# GTL3_Inverter.net
KiCad netlist of a schematic drawn in Altium Designer
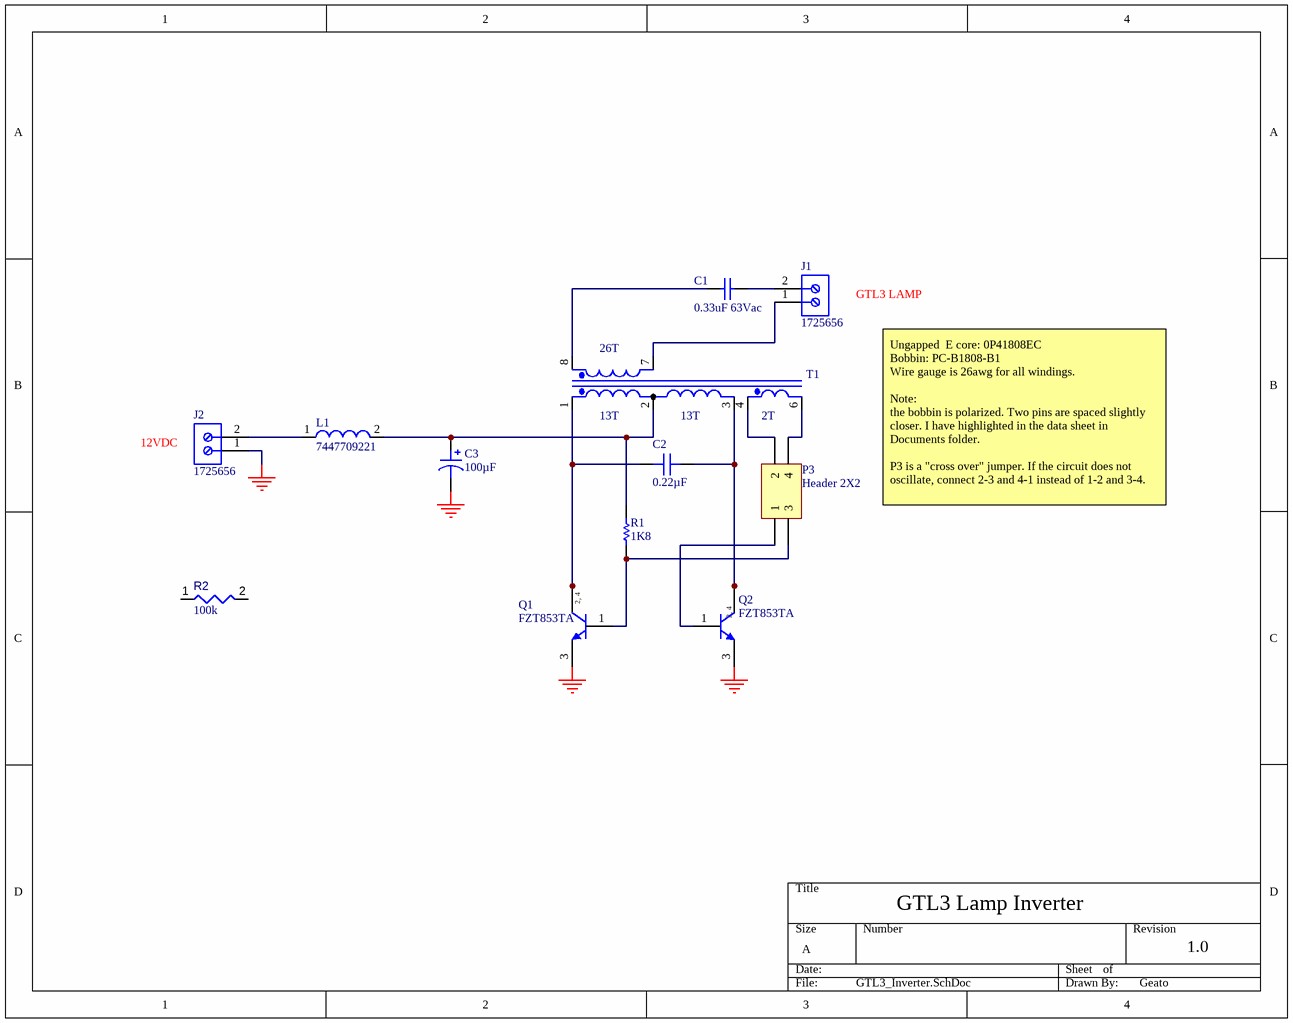
[diagram p0: GTL3_Inverter.SchDoc]

(export (version "E")
  (design (tool "Eeschema 10.0.6"))
  (components
    (comp (ref "C1")
      (value "0.33uF 63Vac")
      (footprint "CAPC6050X33M")
      (description "Film Capacitors 100Vdc 0.33uF 10% AEC-Q200")
      (fields (field (name "TOLERANCE") "10%"))
      (libsource (lib "Greg Eaton") (part "CAP-NP-2"))
    )
    (comp (ref "C2")
      (value "0.22µF")
      (footprint "CAP FILM 2416")
      (description "CAP FILM 0.22UF 2% 50VDC 2416")
      (fields
        (field (name "PART NUMBER") "ECH-U1H224GX9")
        (field (name "MANUFACTURER") "Panasonic Electronic Components")
      )
      (libsource (lib "Celestial Altium Library - altium_library") (part "Capacitor"))
    )
    (comp (ref "C3")
      (value "100µF")
      (footprint "CAP ALSMD 8.3MM H10.5MM")
      (description "CAP ALUM SMD 105C 100UF 50VDC")
      (fields (field (name "PART NUMBER") "EDH107M050A9MAA") (field (name "MANUFACTURER") "KEMET"))
      (libsource (lib "Celestial Altium Library - altium_library") (part "Polarised Capacitor"))
    )
    (comp (ref "J1")
      (value "1725656")
      (footprint "PHOE-1725656-2")
      (description "Male Header, Pitch 2.54 mm, 1 x 2 Position, Height 9 mm, Tail Length 3.5 mm")
      (fields (field (name "MANUFACTURER") "Phoenix Contact"))
      (libsource (lib "Altium Content Vault") (part "CN-1P-F-TB2"))
    )
    (comp (ref "J2")
      (value "1725656")
      (footprint "PHOE-1725656-2")
      (description "Male Header, Pitch 2.54 mm, 1 x 2 Position, Height 9 mm, Tail Length 3.5 mm")
      (fields (field (name "MANUFACTURER") "Phoenix Contact"))
      (libsource (lib "Altium Content Vault") (part "CN-1P-F-TB2"))
    )
    (comp (ref "L1")
      (value "7447709221")
      (footprint "WE-PD-XXL")
      (description "SMD-Shielded Power Inductor WE-PD, L = 220 µH")
      (fields (field (name "AML PART NUMBER") "IND-S0011"))
      (libsource (lib "Altium Content Vault") (part "CMP-0227-00173-1"))
    )
    (comp (ref "P3")
      (value "Header 2X2")
      (footprint "HDR2X2")
      (description "Header, 2-Pin, Dual row")
      (fields (field (name "PUBLISHER") "Altium Limited"))
      (libsource (lib "Miscellaneous Connectors") (part "Header 2X2"))
    )
    (comp (ref "Q1")
      (value "FZT853TA")
      (footprint "DIOD-SOT223-4_V")
      (description "NPN Medium Power Transistor, 100 V, 6 A, -55 to 150 degC, 4-Pin SOT223, RoHS, Tape and Reel")
      (fields (field (name "MANUFACTURER") "DiodesIncorporated"))
      (libsource (lib "Altium Content Vault") (part "BJT-NPN-BCEC-4"))
    )
    (comp (ref "Q2")
      (value "FZT853TA")
      (footprint "DIOD-SOT223-4_V")
      (description "NPN Medium Power Transistor, 100 V, 6 A, -55 to 150 degC, 4-Pin SOT223, RoHS, Tape and Reel")
      (fields (field (name "MANUFACTURER") "DiodesIncorporated"))
      (libsource (lib "Altium Content Vault") (part "BJT-NPN-BCEC-4"))
    )
    (comp (ref "R1")
      (value "1K8")
      (footprint "RESC0805(2012)_L")
      (description "1K8 0.125W 1% 0805 (2012 Metric)  SMD")
      (fields (field (name "POWER") "0.125 W") (field (name "TOLERANCE") "1 %"))
      (libsource (lib "Altium Content Vault") (part "CMP-1013-00537-1"))
    )
    (comp (ref "R2")
      (value "100k")
      (footprint "RESC1608X55X25ML10T15")
      (description "Chip Resistor, 100 KOhm, +/- 1%, 0.1 W, -55 to 155 degC, 0603 (1608 Metric)")
      (fields (field (name "POWER") "100mW") (field (name "TOLERANCE") "1%"))
      (libsource (lib "Greg Eaton") (part "RES-2"))
    )
    (comp (ref "T1")
      (value "Trans5_Royer")
      (footprint "PCB1808B1")
      (description "Four-winding Transformer (Non-Ideal)")
      (fields (field (name "PUBLISHER") "Altium Limited"))
      (libsource (lib "Miscellaneous Devices") (part "Trans5_Royer"))
    )
  )
  (nets
    (net (code "1") (name "GND") (class "Default")
      (node (ref "C3") (pin "2") (pinfunction "2_2") (pintype "passive"))
      (node (ref "J2") (pin "1") (pinfunction "1_1") (pintype "passive"))
      (node (ref "Q1") (pin "3") (pinfunction "E_3") (pintype "passive"))
      (node (ref "Q2") (pin "3") (pinfunction "E_3") (pintype "passive"))
    )
    (net (code "2") (name "Net-(C1-Pad2)") (class "Default")
      (node (ref "C1") (pin "2") (pinfunction "2_2") (pintype "passive"))
      (node (ref "J1") (pin "2") (pinfunction "2_2") (pintype "passive"))
    )
    (net (code "3") (name "Net-(J2-Pad2)") (class "Default")
      (node (ref "J2") (pin "2") (pinfunction "2_2") (pintype "passive"))
      (node (ref "L1") (pin "1") (pinfunction "1_1") (pintype "passive"))
    )
    (net (code "4") (name "Net-(Q1-B)") (class "Default")
      (node (ref "P3") (pin "3") (pinfunction "3_3") (pintype "passive"))
      (node (ref "Q1") (pin "1") (pinfunction "B_1") (pintype "passive"))
      (node (ref "R1") (pin "1") (pinfunction "1_1") (pintype "passive"))
    )
    (net (code "5") (name "Net-(Q2-B)") (class "Default")
      (node (ref "P3") (pin "1") (pinfunction "1_1") (pintype "passive"))
      (node (ref "Q2") (pin "1") (pinfunction "B_1") (pintype "passive"))
    )
    (net (code "6") (name "Net-(T1-Pri+)") (class "Default")
      (node (ref "C1") (pin "1") (pinfunction "1_1") (pintype "passive"))
      (node (ref "T1") (pin "8") (pinfunction "Pri+_8") (pintype "passive"))
    )
    (net (code "7") (name "Net-(T1-Pri-)") (class "Default")
      (node (ref "J1") (pin "1") (pinfunction "1_1") (pintype "passive"))
      (node (ref "T1") (pin "7") (pinfunction "Pri-_7") (pintype "passive"))
    )
    (net (code "8") (name "Net-(T1-Sec1+)") (class "Default")
      (node (ref "C2") (pin "2") (pinfunction "2_2") (pintype "passive"))
      (node (ref "Q1") (pin "2") (pinfunction "C_2") (pintype "passive"))
      (node (ref "Q1") (pin "4") (pinfunction "C_4") (pintype "passive"))
      (node (ref "T1") (pin "1") (pinfunction "Sec1+_1") (pintype "passive"))
    )
    (net (code "9") (name "Net-(T1-Sec1-)") (class "Default")
      (node (ref "C3") (pin "1") (pinfunction "1_1") (pintype "passive"))
      (node (ref "L1") (pin "2") (pinfunction "2_2") (pintype "passive"))
      (node (ref "R1") (pin "2") (pinfunction "2_2") (pintype "passive"))
      (node (ref "T1") (pin "2") (pinfunction "Sec1-_2") (pintype "passive"))
    )
    (net (code "10") (name "Net-(T1-Sec2-)") (class "Default")
      (node (ref "C2") (pin "1") (pinfunction "1_1") (pintype "passive"))
      (node (ref "Q2") (pin "2") (pinfunction "C_2") (pintype "passive"))
      (node (ref "Q2") (pin "4") (pinfunction "C_4") (pintype "passive"))
      (node (ref "T1") (pin "3") (pinfunction "Sec2-_3") (pintype "passive"))
    )
    (net (code "11") (name "Net-(T1-Sec3+)") (class "Default")
      (node (ref "P3") (pin "2") (pinfunction "2_2") (pintype "passive"))
      (node (ref "T1") (pin "4") (pinfunction "Sec3+_4") (pintype "passive"))
    )
    (net (code "12") (name "Net-(T1-Sec3-)") (class "Default")
      (node (ref "P3") (pin "4") (pinfunction "4_4") (pintype "passive"))
      (node (ref "T1") (pin "6") (pinfunction "Sec3-_6") (pintype "passive"))
    )
    (net (code "13") (name "unconnected-(R2-Pad1)") (class "Default")
      (node (ref "R2") (pin "1") (pinfunction "1_1") (pintype "passive"))
    )
    (net (code "14") (name "unconnected-(R2-Pad2)") (class "Default")
      (node (ref "R2") (pin "2") (pinfunction "2_2") (pintype "passive"))
    )
    (net (code "15") (name "unconnected-(T1-Pad5)") (class "Default")
      (node (ref "T1") (pin "5") (pinfunction "5_5") (pintype "passive"))
    )
  )
)
